# Sheet6.net
KiCad netlist of a schematic drawn in Altium Designer
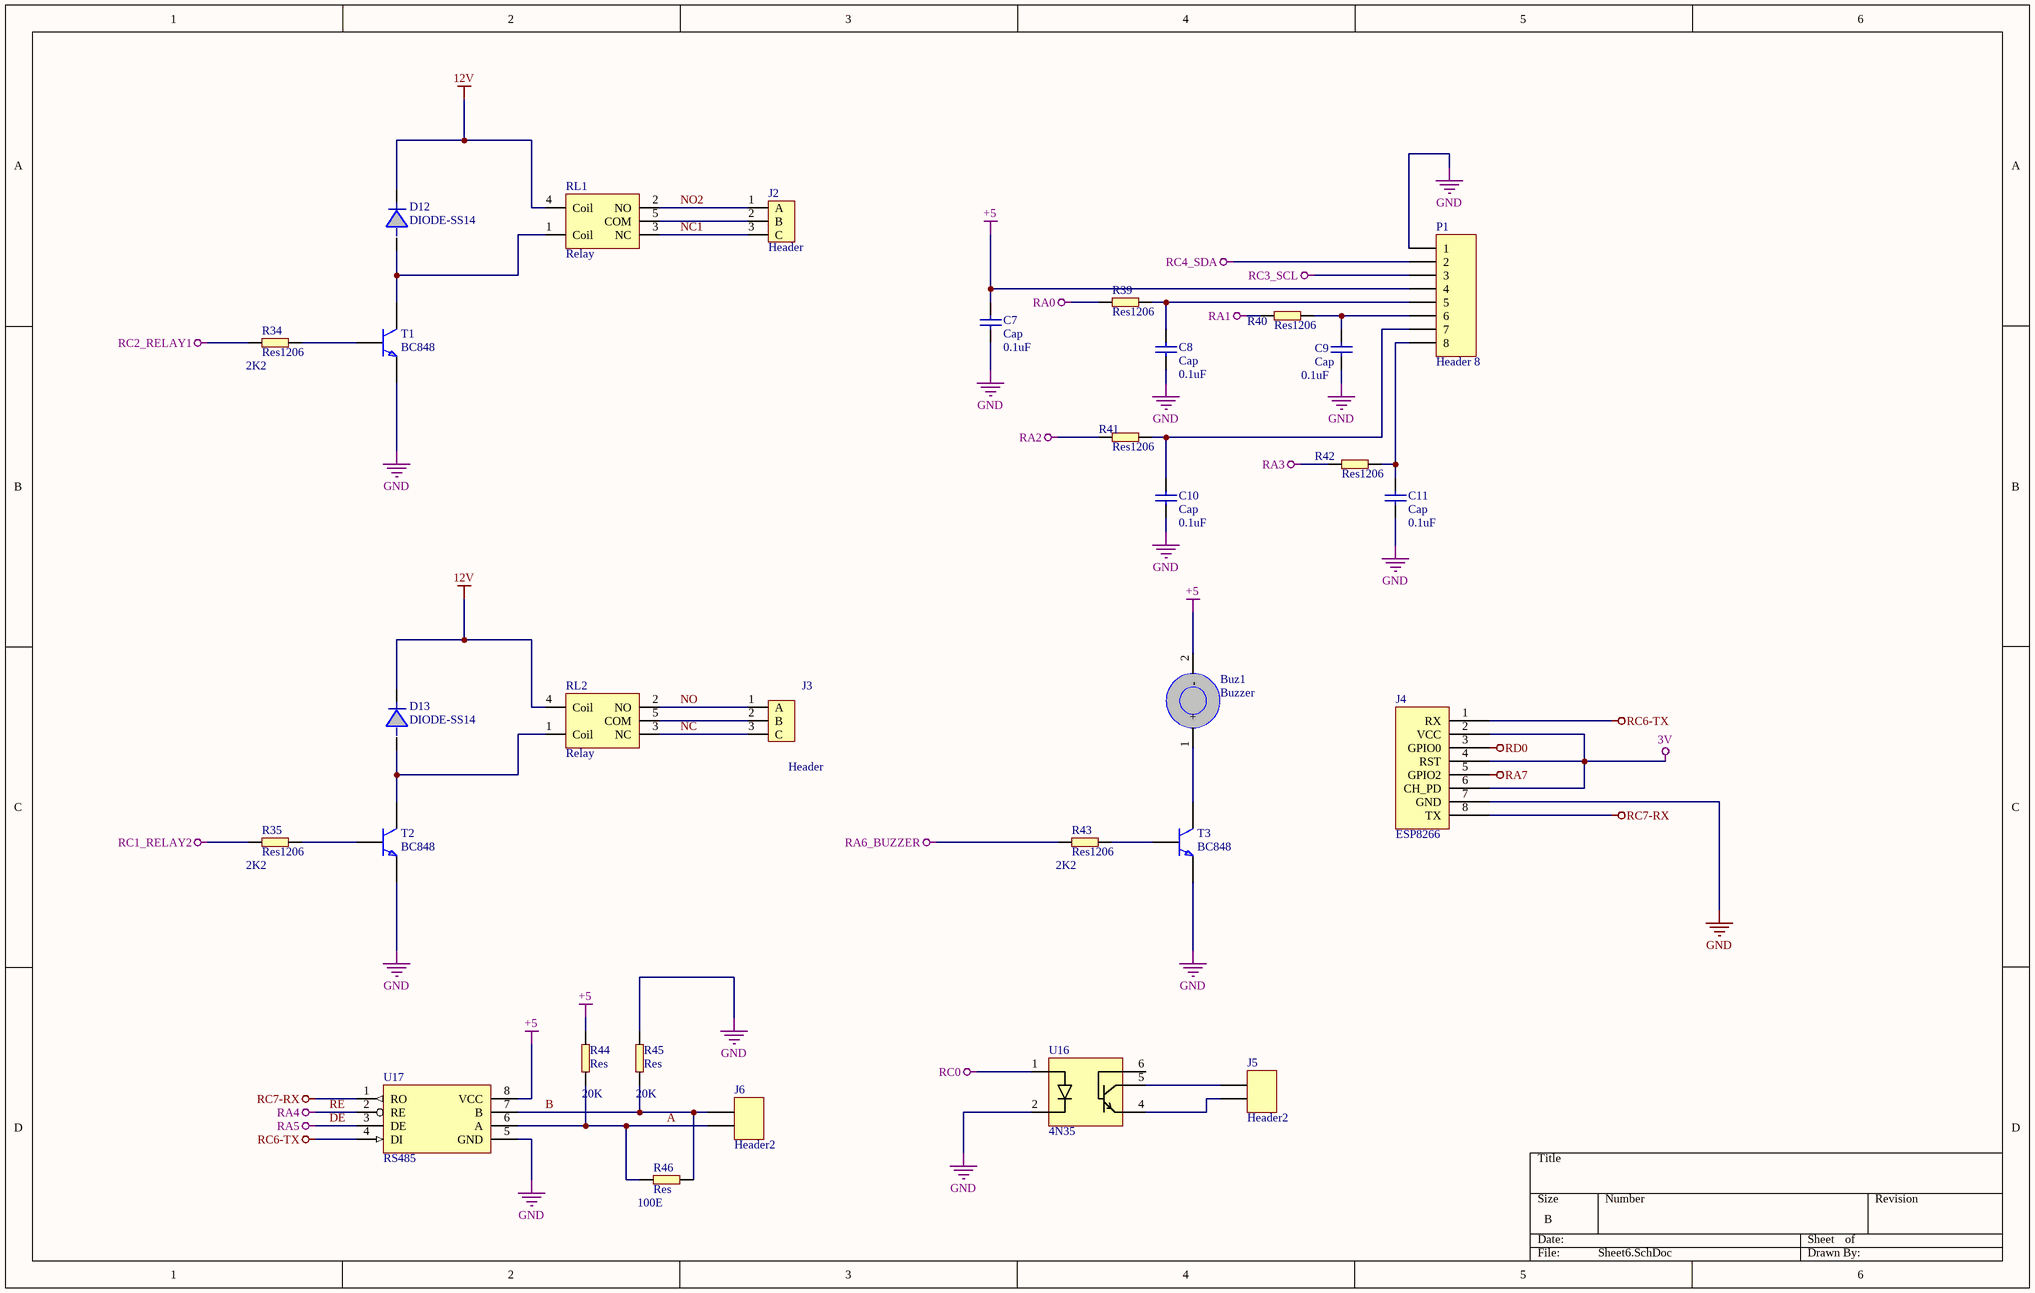
[diagram p0: Sheet6.SchDoc]

(export (version "E")
  (design (tool "Eeschema 10.0.6"))
  (components
    (comp (ref "Buz1")
      (value "Buzzer")
      (footprint "Buzzer")
      (libsource (lib "Dinesh_New_Integrated_Library") (part "Buzzer"))
    )
    (comp (ref "C7")
      (value "Cap")
      (footprint "1206")
      (description "Cap_104_SMD")
      (fields (field (name "ALTIUM_UNNAMED_1") "0.1uF"))
      (libsource (lib "Dinesh_New_Integrated_Library") (part "CAP_104_SMD"))
    )
    (comp (ref "C8")
      (value "Cap")
      (footprint "RES0805")
      (description "Cap_104_SMD")
      (fields (field (name "ALTIUM_UNNAMED_1") "0.1uF"))
      (libsource (lib "Dinesh_New_Integrated_Library") (part "CAP_104_SMD"))
    )
    (comp (ref "C9")
      (value "Cap")
      (footprint "RES0805")
      (description "Cap_104_SMD")
      (fields (field (name "ALTIUM_UNNAMED_1") "0.1uF"))
      (libsource (lib "Dinesh_New_Integrated_Library") (part "CAP_104_SMD"))
    )
    (comp (ref "C10")
      (value "Cap")
      (footprint "RES0805")
      (description "Cap_104_SMD")
      (fields (field (name "ALTIUM_UNNAMED_1") "0.1uF"))
      (libsource (lib "Dinesh_New_Integrated_Library") (part "CAP_104_SMD"))
    )
    (comp (ref "C11")
      (value "Cap")
      (footprint "RES0805")
      (description "Cap_104_SMD")
      (fields (field (name "ALTIUM_UNNAMED_1") "0.1uF"))
      (libsource (lib "Dinesh_New_Integrated_Library") (part "CAP_104_SMD"))
    )
    (comp (ref "D12")
      (value "DIODE-SS14")
      (footprint "DO-214AC")
      (description "SS14")
      (libsource (lib "Dinesh_New_Integrated_Library") (part "DIODE-SS14"))
    )
    (comp (ref "D13")
      (value "DIODE-SS14")
      (footprint "DO-214AC")
      (description "SS14")
      (libsource (lib "Dinesh_New_Integrated_Library") (part "DIODE-SS14"))
    )
    (comp (ref "J2")
      (value "Header")
      (footprint "HEADER AC SMALL")
      (libsource (lib "Dinesh_New_Integrated_Library") (part "HEADER AC SMALL"))
    )
    (comp (ref "J3")
      (value "Header")
      (footprint "HEADER AC SMALL")
      (libsource (lib "Dinesh_New_Integrated_Library") (part "HEADER AC SMALL"))
    )
    (comp (ref "J4")
      (value "ESP8266")
      (footprint "ESP8266")
      (description "WIFI Module")
      (libsource (lib "Dinesh_New_Integrated_Library") (part "ESP8266"))
    )
    (comp (ref "J5")
      (value "Header2")
      (footprint "Header2")
      (libsource (lib "VIJAYIntegrated_Library") (part "Header2"))
    )
    (comp (ref "J6")
      (value "Header2")
      (footprint "Header2")
      (libsource (lib "VIJAYIntegrated_Library") (part "Header2"))
    )
    (comp (ref "P1")
      (value "Header 8")
      (footprint "HDR1X8")
      (description "Header, 8-Pin")
      (fields (field (name "PUBLISHER") "Altium Limited"))
      (libsource (lib "Miscellaneous Connectors") (part "Header 8"))
    )
    (comp (ref "R34")
      (value "Res1206")
      (footprint "1206")
      (fields (field (name "ALTIUM_VALUE") "2K2"))
      (libsource (lib "") (part "Res1206_1"))
    )
    (comp (ref "R35")
      (value "Res1206")
      (footprint "1206")
      (fields (field (name "ALTIUM_VALUE") "2K2"))
      (libsource (lib "") (part "Res1206_1"))
    )
    (comp (ref "R39")
      (value "Res1206")
      (footprint "1206")
      (libsource (lib "Dinesh_New_Integrated_Library") (part "Res1206"))
    )
    (comp (ref "R40")
      (value "Res1206")
      (footprint "1206")
      (libsource (lib "Dinesh_New_Integrated_Library") (part "Res1206"))
    )
    (comp (ref "R41")
      (value "Res1206")
      (footprint "1206")
      (libsource (lib "Dinesh_New_Integrated_Library") (part "Res1206"))
    )
    (comp (ref "R42")
      (value "Res1206")
      (footprint "1206")
      (libsource (lib "Dinesh_New_Integrated_Library") (part "Res1206"))
    )
    (comp (ref "R43")
      (value "Res1206")
      (footprint "1206")
      (fields (field (name "ALTIUM_VALUE") "2K2"))
      (libsource (lib "Dinesh_New_Integrated_Library") (part "Res1206"))
    )
    (comp (ref "R44")
      (value "Res")
      (footprint "RES0805")
      (description "Res0805")
      (fields (field (name "ALTIUM_VALUE") "20K"))
      (libsource (lib "Dinesh_New_Integrated_Library") (part "Resistor"))
    )
    (comp (ref "R45")
      (value "Res")
      (footprint "RES0805")
      (description "Res0805")
      (fields (field (name "ALTIUM_VALUE") "20K"))
      (libsource (lib "Dinesh_New_Integrated_Library") (part "Resistor"))
    )
    (comp (ref "R46")
      (value "Res")
      (footprint "RES0805")
      (description "Res0805")
      (fields (field (name "ALTIUM_VALUE") "100E"))
      (libsource (lib "") (part "Resistor_1"))
    )
    (comp (ref "RL1")
      (value "Relay")
      (footprint "Relay")
      (description "Relay 12V")
      (libsource (lib "Dinesh_New_Integrated_Library") (part "Relay"))
    )
    (comp (ref "RL2")
      (value "Relay")
      (footprint "Relay")
      (description "Relay 12V")
      (libsource (lib "Dinesh_New_Integrated_Library") (part "Relay"))
    )
    (comp (ref "T1")
      (value "BC848")
      (footprint "SOT23")
      (description "TRANSISTOR")
      (libsource (lib "Dinesh_New_Integrated_Library") (part "BC848"))
    )
    (comp (ref "T2")
      (value "BC848")
      (footprint "SOT23")
      (description "TRANSISTOR")
      (libsource (lib "Dinesh_New_Integrated_Library") (part "BC848"))
    )
    (comp (ref "T3")
      (value "BC848")
      (footprint "SOT23")
      (description "TRANSISTOR")
      (libsource (lib "Dinesh_New_Integrated_Library") (part "BC848"))
    )
    (comp (ref "U16")
      (value "4N35")
      (footprint "4N35")
      (description "Optocoupler")
      (libsource (lib "Dinesh_New_Integrated_Library") (part "4N35"))
    )
    (comp (ref "U17")
      (value "RS485")
      (footprint "RS485")
      (description "8-Pin SO")
      (libsource (lib "VIJAYIntegrated_Library") (part "RS485"))
    )
  )
  (nets
    (net (code "1") (name "+5") (class "Default")
      (node (ref "Buz1") (pin "2") (pinfunction "-_2") (pintype "passive"))
      (node (ref "C7") (pin "2") (pinfunction "A_2") (pintype "passive"))
      (node (ref "P1") (pin "4") (pinfunction "4_4") (pintype "passive"))
      (node (ref "R44") (pin "2") (pinfunction "b_2") (pintype "passive"))
      (node (ref "U17") (pin "8") (pinfunction "VCC_8") (pintype "passive"))
    )
    (net (code "2") (name "/A") (class "Default")
      (node (ref "J6") (pin "2") (pinfunction "2_2") (pintype "power_in"))
      (node (ref "R44") (pin "1") (pinfunction "a_1") (pintype "passive"))
      (node (ref "R46") (pin "1") (pinfunction "a_1") (pintype "passive"))
      (node (ref "U17") (pin "6") (pinfunction "A_6") (pintype "passive"))
    )
    (net (code "3") (name "/B") (class "Default")
      (node (ref "J6") (pin "1") (pinfunction "1_1") (pintype "power_in"))
      (node (ref "R45") (pin "1") (pinfunction "a_1") (pintype "passive"))
      (node (ref "R46") (pin "2") (pinfunction "b_2") (pintype "passive"))
      (node (ref "U17") (pin "7") (pinfunction "B_7") (pintype "passive"))
    )
    (net (code "4") (name "/NC") (class "Default")
      (node (ref "J3") (pin "3") (pinfunction "C_3") (pintype "passive"))
      (node (ref "RL2") (pin "3") (pinfunction "NC_3") (pintype "passive"))
    )
    (net (code "5") (name "/NC1") (class "Default")
      (node (ref "J2") (pin "3") (pinfunction "C_3") (pintype "passive"))
      (node (ref "RL1") (pin "3") (pinfunction "NC_3") (pintype "passive"))
    )
    (net (code "6") (name "/NO") (class "Default")
      (node (ref "J3") (pin "1") (pinfunction "A_1") (pintype "passive"))
      (node (ref "RL2") (pin "2") (pinfunction "NO_2") (pintype "passive"))
    )
    (net (code "7") (name "/NO2") (class "Default")
      (node (ref "J2") (pin "1") (pinfunction "A_1") (pintype "passive"))
      (node (ref "RL1") (pin "2") (pinfunction "NO_2") (pintype "passive"))
    )
    (net (code "8") (name "3V") (class "Default")
      (node (ref "J4") (pin "2") (pinfunction "VCC_2") (pintype "passive"))
      (node (ref "J4") (pin "4") (pinfunction "RST_4") (pintype "passive"))
      (node (ref "J4") (pin "6") (pinfunction "CH_PD_6") (pintype "passive"))
    )
    (net (code "9") (name "12V") (class "Default")
      (node (ref "D12") (pin "2") (pinfunction "B_2") (pintype "passive"))
      (node (ref "D13") (pin "2") (pinfunction "B_2") (pintype "passive"))
      (node (ref "RL1") (pin "4") (pinfunction "Coil_4") (pintype "passive"))
      (node (ref "RL2") (pin "4") (pinfunction "Coil_4") (pintype "passive"))
    )
    (net (code "10") (name "GND") (class "Default")
      (node (ref "C10") (pin "1") (pinfunction "A_1") (pintype "passive"))
      (node (ref "C11") (pin "1") (pinfunction "A_1") (pintype "passive"))
      (node (ref "C7") (pin "1") (pinfunction "A_1") (pintype "passive"))
      (node (ref "C8") (pin "1") (pinfunction "A_1") (pintype "passive"))
      (node (ref "C9") (pin "1") (pinfunction "A_1") (pintype "passive"))
      (node (ref "J4") (pin "7") (pinfunction "GND_7") (pintype "passive"))
      (node (ref "P1") (pin "1") (pinfunction "1_1") (pintype "passive"))
      (node (ref "R45") (pin "2") (pinfunction "b_2") (pintype "passive"))
      (node (ref "T1") (pin "2") (pinfunction "E_2") (pintype "passive"))
      (node (ref "T2") (pin "2") (pinfunction "E_2") (pintype "passive"))
      (node (ref "T3") (pin "2") (pinfunction "E_2") (pintype "passive"))
      (node (ref "U16") (pin "2") (pinfunction "B_2") (pintype "passive"))
      (node (ref "U17") (pin "5") (pinfunction "GND_5") (pintype "passive"))
    )
    (net (code "11") (name "Net-(Buz1-+)") (class "Default")
      (node (ref "Buz1") (pin "1") (pinfunction "+_1") (pintype "passive"))
      (node (ref "T3") (pin "3") (pinfunction "C_3") (pintype "passive"))
    )
    (net (code "12") (name "Net-(D12-A)") (class "Default")
      (node (ref "D12") (pin "1") (pinfunction "A_1") (pintype "passive"))
      (node (ref "RL1") (pin "1") (pinfunction "Coil_1") (pintype "passive"))
      (node (ref "T1") (pin "3") (pinfunction "C_3") (pintype "passive"))
    )
    (net (code "13") (name "Net-(D13-A)") (class "Default")
      (node (ref "D13") (pin "1") (pinfunction "A_1") (pintype "passive"))
      (node (ref "RL2") (pin "1") (pinfunction "Coil_1") (pintype "passive"))
      (node (ref "T2") (pin "3") (pinfunction "C_3") (pintype "passive"))
    )
    (net (code "14") (name "Net-(J2-B)") (class "Default")
      (node (ref "J2") (pin "2") (pinfunction "B_2") (pintype "passive"))
      (node (ref "RL1") (pin "5") (pinfunction "COM_5") (pintype "passive"))
    )
    (net (code "15") (name "Net-(J3-B)") (class "Default")
      (node (ref "J3") (pin "2") (pinfunction "B_2") (pintype "passive"))
      (node (ref "RL2") (pin "5") (pinfunction "COM_5") (pintype "passive"))
    )
    (net (code "16") (name "Net-(R34-b)") (class "Default")
      (node (ref "R34") (pin "2") (pinfunction "b_2") (pintype "passive"))
      (node (ref "T1") (pin "1") (pinfunction "B_1") (pintype "passive"))
    )
    (net (code "17") (name "Net-(R35-b)") (class "Default")
      (node (ref "R35") (pin "2") (pinfunction "b_2") (pintype "passive"))
      (node (ref "T2") (pin "1") (pinfunction "B_1") (pintype "passive"))
    )
    (net (code "18") (name "Net-(R39-a)") (class "Default")
      (node (ref "C8") (pin "2") (pinfunction "A_2") (pintype "passive"))
      (node (ref "P1") (pin "5") (pinfunction "5_5") (pintype "passive"))
      (node (ref "R39") (pin "1") (pinfunction "a_1") (pintype "passive"))
    )
    (net (code "19") (name "Net-(R40-a)") (class "Default")
      (node (ref "C9") (pin "2") (pinfunction "A_2") (pintype "passive"))
      (node (ref "P1") (pin "6") (pinfunction "6_6") (pintype "passive"))
      (node (ref "R40") (pin "1") (pinfunction "a_1") (pintype "passive"))
    )
    (net (code "20") (name "Net-(R41-a)") (class "Default")
      (node (ref "C10") (pin "2") (pinfunction "A_2") (pintype "passive"))
      (node (ref "P1") (pin "7") (pinfunction "7_7") (pintype "passive"))
      (node (ref "R41") (pin "1") (pinfunction "a_1") (pintype "passive"))
    )
    (net (code "21") (name "Net-(R42-a)") (class "Default")
      (node (ref "C11") (pin "2") (pinfunction "A_2") (pintype "passive"))
      (node (ref "P1") (pin "8") (pinfunction "8_8") (pintype "passive"))
      (node (ref "R42") (pin "1") (pinfunction "a_1") (pintype "passive"))
    )
    (net (code "22") (name "Net-(R43-a)") (class "Default")
      (node (ref "R43") (pin "1") (pinfunction "a_1") (pintype "passive"))
      (node (ref "T3") (pin "1") (pinfunction "B_1") (pintype "passive"))
    )
    (net (code "23") (name "Net-(U16-D)") (class "Default")
      (node (ref "J5") (pin "2") (pinfunction "2_2") (pintype "power_in"))
      (node (ref "U16") (pin "4") (pinfunction "D_4") (pintype "passive"))
    )
    (net (code "24") (name "Net-(U16-E)") (class "Default")
      (node (ref "J5") (pin "1") (pinfunction "1_1") (pintype "power_in"))
      (node (ref "U16") (pin "5") (pinfunction "E_5") (pintype "passive"))
    )
    (net (code "25") (name "RA0") (class "Default")
      (node (ref "R39") (pin "2") (pinfunction "b_2") (pintype "passive"))
    )
    (net (code "26") (name "RA1") (class "Default")
      (node (ref "R40") (pin "2") (pinfunction "b_2") (pintype "passive"))
    )
    (net (code "27") (name "RA2") (class "Default")
      (node (ref "R41") (pin "2") (pinfunction "b_2") (pintype "passive"))
    )
    (net (code "28") (name "RA3") (class "Default")
      (node (ref "R42") (pin "2") (pinfunction "b_2") (pintype "passive"))
    )
    (net (code "29") (name "RA4") (class "Default")
      (node (ref "U17") (pin "2") (pinfunction "RE_2") (pintype "passive"))
    )
    (net (code "30") (name "RA5") (class "Default")
      (node (ref "U17") (pin "3") (pinfunction "DE_3") (pintype "passive"))
    )
    (net (code "31") (name "RA6_BUZZER") (class "Default")
      (node (ref "R43") (pin "2") (pinfunction "b_2") (pintype "passive"))
    )
    (net (code "32") (name "RA7") (class "Default")
      (node (ref "J4") (pin "5") (pinfunction "GPIO2_5") (pintype "passive"))
    )
    (net (code "33") (name "RC0") (class "Default")
      (node (ref "U16") (pin "1") (pinfunction "A_1") (pintype "passive"))
    )
    (net (code "34") (name "RC1_RELAY2") (class "Default")
      (node (ref "R35") (pin "1") (pinfunction "a_1") (pintype "passive"))
    )
    (net (code "35") (name "RC2_RELAY1") (class "Default")
      (node (ref "R34") (pin "1") (pinfunction "a_1") (pintype "passive"))
    )
    (net (code "36") (name "RC3_SCL") (class "Default")
      (node (ref "P1") (pin "3") (pinfunction "3_3") (pintype "passive"))
    )
    (net (code "37") (name "RC4_SDA") (class "Default")
      (node (ref "P1") (pin "2") (pinfunction "2_2") (pintype "passive"))
    )
    (net (code "38") (name "RC6-TX") (class "Default")
      (node (ref "J4") (pin "1") (pinfunction "RX_1") (pintype "passive"))
      (node (ref "U17") (pin "4") (pinfunction "DI_4") (pintype "input"))
    )
    (net (code "39") (name "RC7-RX") (class "Default")
      (node (ref "J4") (pin "8") (pinfunction "TX_8") (pintype "passive"))
      (node (ref "U17") (pin "1") (pinfunction "RO_1") (pintype "output"))
    )
    (net (code "40") (name "RD0") (class "Default")
      (node (ref "J4") (pin "3") (pinfunction "GPIO0_3") (pintype "passive"))
    )
    (net (code "41") (name "unconnected-(U16-F-Pad6)") (class "Default")
      (node (ref "U16") (pin "6") (pinfunction "F_6") (pintype "passive"))
    )
  )
)
